# ik_dragonfly.net
KiCad netlist of a schematic drawn in EAGLE
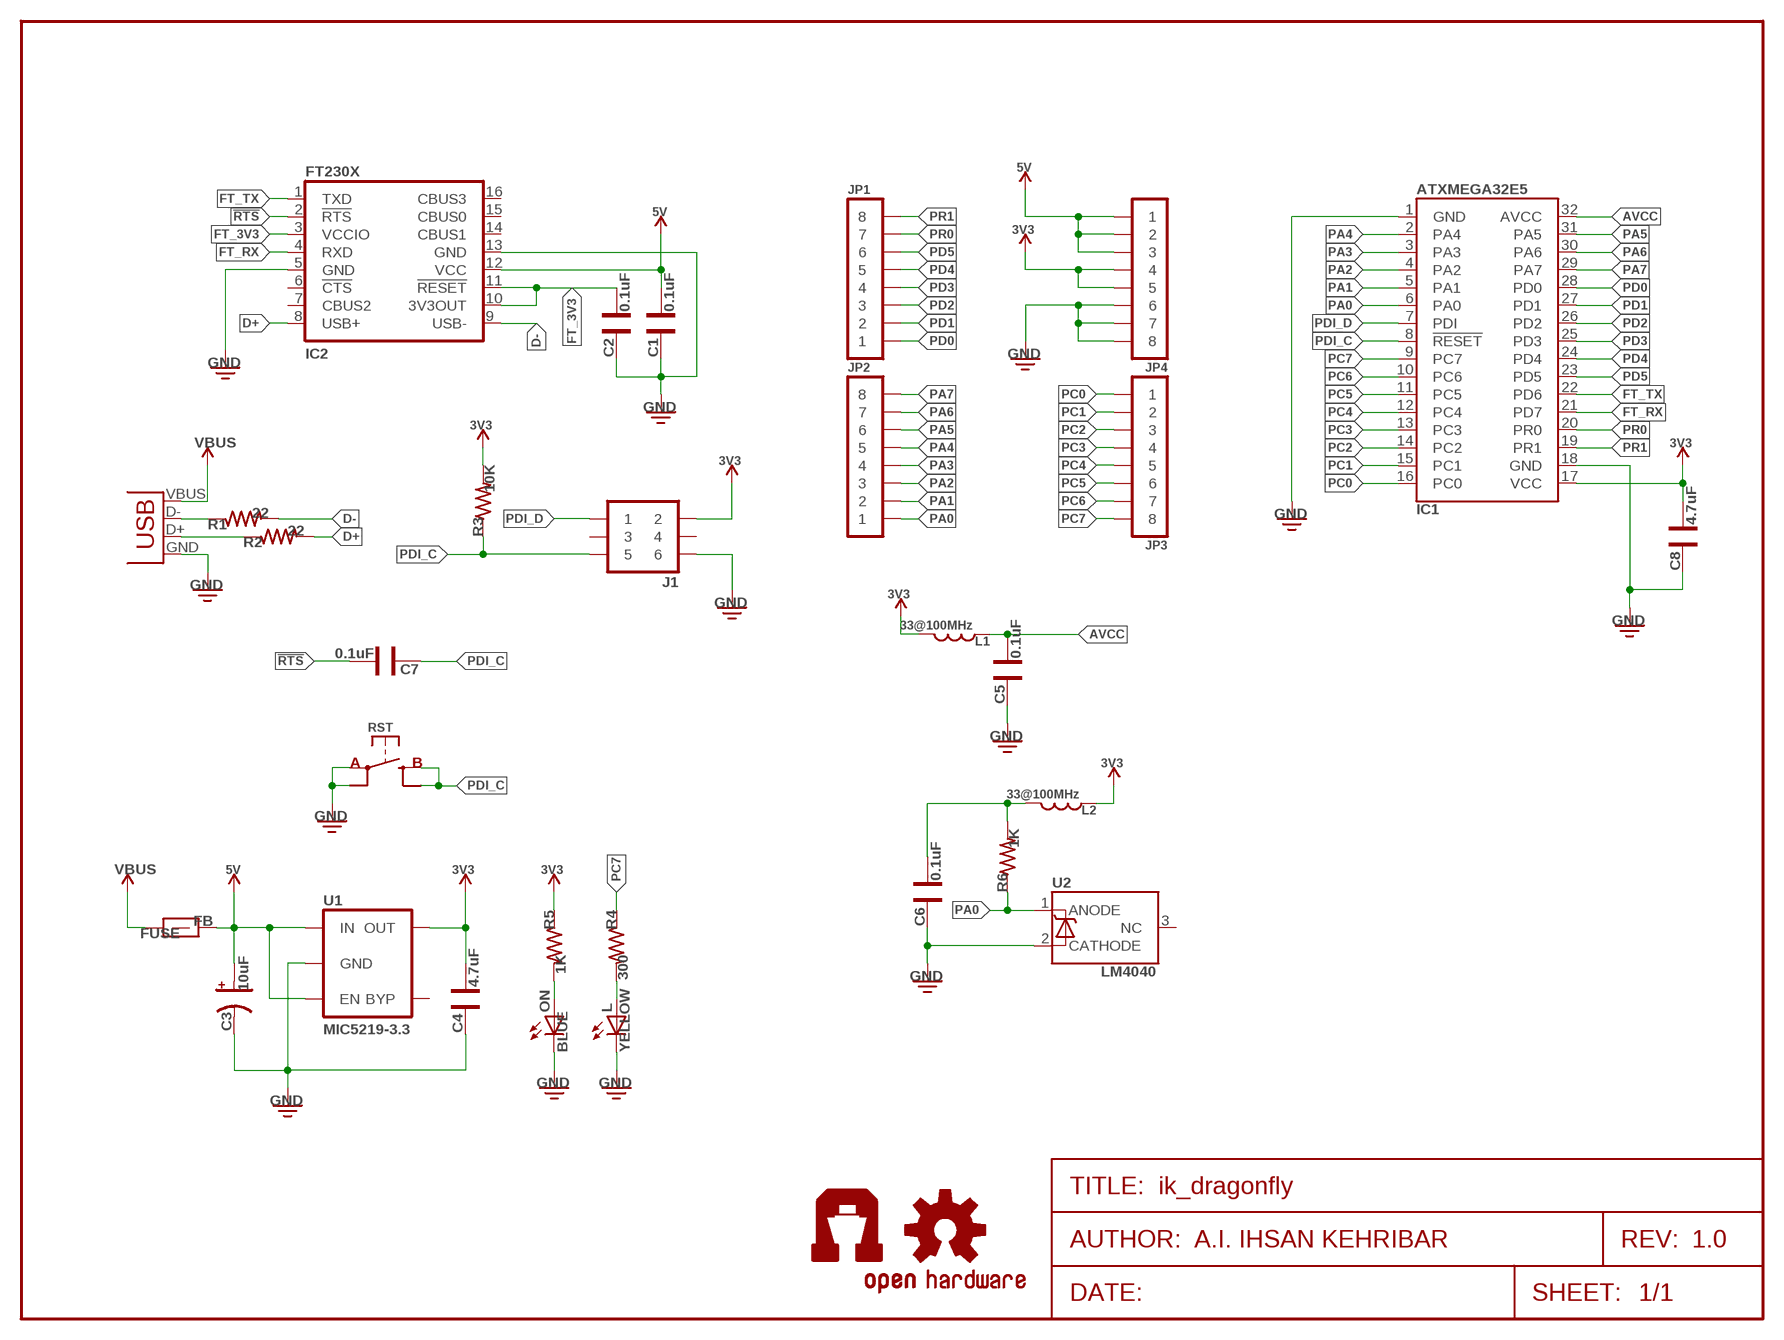
[diagram p0: schematic, sheet 1]

(export (version "E")
  (design (tool "Eeschema 10.0.6"))
  (components
    (comp (ref "C1")
      (value "0.1uF")
      (footprint "eagle-import:CAP-0603")
      (libsource (lib "eagle-import") (part "CAP0603"))
    )
    (comp (ref "C2")
      (value "0.1uF")
      (footprint "eagle-import:CAP-0603")
      (libsource (lib "eagle-import") (part "CAP0603"))
    )
    (comp (ref "C3")
      (value "10uF")
      (footprint "eagle-import:CAP-POL-EIA3216")
      (libsource (lib "eagle-import") (part "CAP-POLEIA3216"))
    )
    (comp (ref "C4")
      (value "4.7uF")
      (footprint "eagle-import:CAP-0603")
      (libsource (lib "eagle-import") (part "CAP0603"))
    )
    (comp (ref "C5")
      (value "0.1uF")
      (footprint "eagle-import:CAP-0603")
      (libsource (lib "eagle-import") (part "CAP0603"))
    )
    (comp (ref "C6")
      (value "0.1uF")
      (footprint "eagle-import:CAP-0603")
      (libsource (lib "eagle-import") (part "CAP0603"))
    )
    (comp (ref "C7")
      (value "0.1uF")
      (footprint "eagle-import:CAP-0603")
      (libsource (lib "eagle-import") (part "CAP0603"))
    )
    (comp (ref "C8")
      (value "4.7uF")
      (footprint "eagle-import:CAP-0603")
      (libsource (lib "eagle-import") (part "CAP0603"))
    )
    (comp (ref "FUSE")
      (value "FB")
      (footprint "eagle-import:FB-0603")
      (libsource (lib "eagle-import") (part "FB"))
    )
    (comp (ref "IC1")
      (value "ATXMEGA32E5")
      (footprint "eagle-import:TQFP32-08")
      (libsource (lib "eagle-import") (part "ATXMEGA32E5"))
    )
    (comp (ref "IC2")
      (value "FT230X")
      (footprint "eagle-import:SSOP-16-FTDI")
      (libsource (lib "eagle-import") (part "FT230X"))
    )
    (comp (ref "J1")
      (value "2X03")
      (footprint "eagle-import:2X03")
      (libsource (lib "eagle-import") (part "2X03"))
    )
    (comp (ref "JP1")
      (value "1X08NOFIRST")
      (footprint "eagle-import:1X08-NOFIRST")
      (libsource (lib "eagle-import") (part "1X08NOFIRST"))
    )
    (comp (ref "JP2")
      (value "1X08NOFIRST")
      (footprint "eagle-import:1X08-NOFIRST")
      (libsource (lib "eagle-import") (part "1X08NOFIRST"))
    )
    (comp (ref "JP3")
      (value "1X08NOFIRST")
      (footprint "eagle-import:1X08-NOFIRST")
      (libsource (lib "eagle-import") (part "1X08NOFIRST"))
    )
    (comp (ref "JP4")
      (value "1X08NOFIRST")
      (footprint "eagle-import:1X08-NOFIRST")
      (libsource (lib "eagle-import") (part "1X08NOFIRST"))
    )
    (comp (ref "L")
      (value "YELLOW")
      (footprint "eagle-import:LED-0603")
      (libsource (lib "eagle-import") (part "LED0603"))
    )
    (comp (ref "L1")
      (value "33@100MHz")
      (footprint "eagle-import:IND-0603")
      (libsource (lib "eagle-import") (part "IND0603"))
    )
    (comp (ref "L2")
      (value "33@100MHz")
      (footprint "eagle-import:IND-0603")
      (libsource (lib "eagle-import") (part "IND0603"))
    )
    (comp (ref "LOGO1")
      (value "OSHW-LOGOS")
      (footprint "eagle-import:OSHW-LOGO-S")
      (libsource (lib "eagle-import") (part "OSHW-LOGOS"))
    )
    (comp (ref "ON")
      (value "BLUE")
      (footprint "eagle-import:LED-0603")
      (libsource (lib "eagle-import") (part "LED0603"))
    )
    (comp (ref "R1")
      (value "22")
      (footprint "eagle-import:RES-0603")
      (libsource (lib "eagle-import") (part "RES0603"))
    )
    (comp (ref "R2")
      (value "22")
      (footprint "eagle-import:RES-0603")
      (libsource (lib "eagle-import") (part "RES0603"))
    )
    (comp (ref "R3")
      (value "10K")
      (footprint "eagle-import:RES-0603")
      (libsource (lib "eagle-import") (part "RES0603"))
    )
    (comp (ref "R4")
      (value "300")
      (footprint "eagle-import:RES-0603")
      (libsource (lib "eagle-import") (part "RES0603"))
    )
    (comp (ref "R5")
      (value "1K")
      (footprint "eagle-import:RES-0603")
      (libsource (lib "eagle-import") (part "RES0603"))
    )
    (comp (ref "R6")
      (value "1K")
      (footprint "eagle-import:RES-0603")
      (libsource (lib "eagle-import") (part "RES0603"))
    )
    (comp (ref "RST")
      (value "SW-SPSTSMD035X030")
      (footprint "eagle-import:SW-SPST-SMD035X030")
      (libsource (lib "eagle-import") (part "SW-SPSTSMD035X030"))
    )
    (comp (ref "U$3")
      (value "AI-LOGOXS")
      (footprint "eagle-import:AI-LOGO-XS")
      (libsource (lib "eagle-import") (part "AI-LOGOXS"))
    )
    (comp (ref "U1")
      (value "MIC5219-3.3")
      (footprint "eagle-import:SOT23-5")
      (libsource (lib "eagle-import") (part "MIC5219-3.3"))
    )
    (comp (ref "U2")
      (value "LM4040")
      (footprint "eagle-import:SOT23-3")
      (libsource (lib "eagle-import") (part "LM4040"))
    )
    (comp (ref "USB1")
      (value "USBMICROB-TH")
      (footprint "eagle-import:USB-MICROB-TH")
      (libsource (lib "eagle-import") (part "USBMICROB-TH"))
    )
  )
  (nets
    (net (code "1") (name "/~{RTS}") (class "Default")
      (node (ref "C7") (pin "1") (pinfunction "1_1") (pintype "passive"))
      (node (ref "IC2") (pin "2") (pinfunction "~{RTS}_2") (pintype "bidirectional"))
    )
    (net (code "2") (name "3V3") (class "Default")
      (node (ref "C4") (pin "1") (pinfunction "1_1") (pintype "passive"))
      (node (ref "C8") (pin "1") (pinfunction "1_1") (pintype "passive"))
      (node (ref "IC1") (pin "17") (pinfunction "VCC_17") (pintype "bidirectional"))
      (node (ref "J1") (pin "2") (pinfunction "2_2") (pintype "bidirectional"))
      (node (ref "JP4") (pin "4") (pinfunction "4_4") (pintype "bidirectional"))
      (node (ref "JP4") (pin "5") (pinfunction "5_5") (pintype "bidirectional"))
      (node (ref "L1") (pin "1") (pinfunction "1_1") (pintype "passive"))
      (node (ref "L2") (pin "2") (pinfunction "2_2") (pintype "passive"))
      (node (ref "R3") (pin "2") (pinfunction "2_2") (pintype "passive"))
      (node (ref "R5") (pin "1") (pinfunction "1_1") (pintype "passive"))
      (node (ref "U1") (pin "5") (pinfunction "OUT_5") (pintype "passive"))
    )
    (net (code "3") (name "5V") (class "Default")
      (node (ref "C1") (pin "1") (pinfunction "1_1") (pintype "passive"))
      (node (ref "C3") (pin "A") (pinfunction "A_A") (pintype "passive"))
      (node (ref "FUSE") (pin "2") (pinfunction "P$2_2") (pintype "bidirectional"))
      (node (ref "IC2") (pin "12") (pinfunction "VCC_12") (pintype "power_in"))
      (node (ref "JP4") (pin "1") (pinfunction "1_1") (pintype "bidirectional"))
      (node (ref "JP4") (pin "2") (pinfunction "2_2") (pintype "bidirectional"))
      (node (ref "JP4") (pin "3") (pinfunction "3_3") (pintype "bidirectional"))
      (node (ref "U1") (pin "1") (pinfunction "IN_1") (pintype "input"))
      (node (ref "U1") (pin "3") (pinfunction "EN_3") (pintype "input"))
    )
    (net (code "4") (name "AVCC") (class "Default")
      (node (ref "C5") (pin "1") (pinfunction "1_1") (pintype "passive"))
      (node (ref "IC1") (pin "32") (pinfunction "AVCC_32") (pintype "bidirectional"))
      (node (ref "L1") (pin "2") (pinfunction "2_2") (pintype "passive"))
    )
    (net (code "5") (name "D+") (class "Default")
      (node (ref "IC2") (pin "8") (pinfunction "USB+_8") (pintype "output"))
      (node (ref "R2") (pin "2") (pinfunction "2_2") (pintype "passive"))
    )
    (net (code "6") (name "D-") (class "Default")
      (node (ref "IC2") (pin "9") (pinfunction "USB-_9") (pintype "input"))
      (node (ref "R1") (pin "2") (pinfunction "2_2") (pintype "passive"))
    )
    (net (code "7") (name "FT_3V3") (class "Default")
      (node (ref "C2") (pin "1") (pinfunction "1_1") (pintype "passive"))
      (node (ref "IC2") (pin "10") (pinfunction "3V3OUT_10") (pintype "power_in"))
      (node (ref "IC2") (pin "11") (pinfunction "~{RESET}_11") (pintype "bidirectional"))
      (node (ref "IC2") (pin "3") (pinfunction "VCCIO_3") (pintype "power_in"))
    )
    (net (code "8") (name "FT_RX") (class "Default")
      (node (ref "IC1") (pin "21") (pinfunction "PD7_21") (pintype "bidirectional"))
      (node (ref "IC2") (pin "4") (pinfunction "RXD_4") (pintype "input"))
    )
    (net (code "9") (name "FT_TX") (class "Default")
      (node (ref "IC1") (pin "22") (pinfunction "PD6_22") (pintype "bidirectional"))
      (node (ref "IC2") (pin "1") (pinfunction "TXD_1") (pintype "output"))
    )
    (net (code "10") (name "GND") (class "Default")
      (node (ref "C1") (pin "2") (pinfunction "2_2") (pintype "passive"))
      (node (ref "C2") (pin "2") (pinfunction "2_2") (pintype "passive"))
      (node (ref "C3") (pin "C") (pinfunction "C_C") (pintype "passive"))
      (node (ref "C4") (pin "2") (pinfunction "2_2") (pintype "passive"))
      (node (ref "C5") (pin "2") (pinfunction "2_2") (pintype "passive"))
      (node (ref "C6") (pin "2") (pinfunction "2_2") (pintype "passive"))
      (node (ref "C8") (pin "2") (pinfunction "2_2") (pintype "passive"))
      (node (ref "IC1") (pin "1") (pinfunction "GND_1") (pintype "bidirectional"))
      (node (ref "IC1") (pin "18") (pinfunction "GND_18") (pintype "bidirectional"))
      (node (ref "IC2") (pin "13") (pinfunction "GND_13") (pintype "power_in"))
      (node (ref "IC2") (pin "5") (pinfunction "GND_5") (pintype "power_in"))
      (node (ref "J1") (pin "6") (pinfunction "6_6") (pintype "bidirectional"))
      (node (ref "JP4") (pin "6") (pinfunction "6_6") (pintype "bidirectional"))
      (node (ref "JP4") (pin "7") (pinfunction "7_7") (pintype "bidirectional"))
      (node (ref "JP4") (pin "8") (pinfunction "8_8") (pintype "bidirectional"))
      (node (ref "L") (pin "C") (pinfunction "C_C") (pintype "passive"))
      (node (ref "ON") (pin "C") (pinfunction "C_C") (pintype "passive"))
      (node (ref "RST") (pin "1") (pinfunction "A_1") (pintype "passive"))
      (node (ref "RST") (pin "2") (pinfunction "A_2") (pintype "passive"))
      (node (ref "U1") (pin "2") (pinfunction "GND_2") (pintype "input"))
      (node (ref "U2") (pin "2") (pinfunction "CATHODE_2") (pintype "bidirectional"))
      (node (ref "USB1") (pin "GND") (pinfunction "GND_GND") (pintype "bidirectional"))
    )
    (net (code "11") (name "Net-(C6-Pad1)") (class "Default")
      (node (ref "C6") (pin "1") (pinfunction "1_1") (pintype "passive"))
      (node (ref "L2") (pin "1") (pinfunction "1_1") (pintype "passive"))
      (node (ref "R6") (pin "2") (pinfunction "2_2") (pintype "passive"))
    )
    (net (code "12") (name "Net-(L-PadA)") (class "Default")
      (node (ref "L") (pin "A") (pinfunction "A_A") (pintype "passive"))
      (node (ref "R4") (pin "2") (pinfunction "2_2") (pintype "passive"))
    )
    (net (code "13") (name "Net-(ON-PadA)") (class "Default")
      (node (ref "ON") (pin "A") (pinfunction "A_A") (pintype "passive"))
      (node (ref "R5") (pin "2") (pinfunction "2_2") (pintype "passive"))
    )
    (net (code "14") (name "Net-(R1-Pad1)") (class "Default")
      (node (ref "R1") (pin "1") (pinfunction "1_1") (pintype "passive"))
      (node (ref "USB1") (pin "D-") (pinfunction "D-_D-") (pintype "bidirectional"))
    )
    (net (code "15") (name "Net-(R2-Pad1)") (class "Default")
      (node (ref "R2") (pin "1") (pinfunction "1_1") (pintype "passive"))
      (node (ref "USB1") (pin "D+") (pinfunction "D+_D+") (pintype "bidirectional"))
    )
    (net (code "16") (name "PA0") (class "Default")
      (node (ref "IC1") (pin "6") (pinfunction "PA0_6") (pintype "bidirectional"))
      (node (ref "JP2") (pin "1") (pinfunction "1_1") (pintype "bidirectional"))
      (node (ref "R6") (pin "1") (pinfunction "1_1") (pintype "passive"))
      (node (ref "U2") (pin "1") (pinfunction "ANODE_1") (pintype "bidirectional"))
    )
    (net (code "17") (name "PA1") (class "Default")
      (node (ref "IC1") (pin "5") (pinfunction "PA1_5") (pintype "bidirectional"))
      (node (ref "JP2") (pin "2") (pinfunction "2_2") (pintype "bidirectional"))
    )
    (net (code "18") (name "PA2") (class "Default")
      (node (ref "IC1") (pin "4") (pinfunction "PA2_4") (pintype "bidirectional"))
      (node (ref "JP2") (pin "3") (pinfunction "3_3") (pintype "bidirectional"))
    )
    (net (code "19") (name "PA3") (class "Default")
      (node (ref "IC1") (pin "3") (pinfunction "PA3_3") (pintype "bidirectional"))
      (node (ref "JP2") (pin "4") (pinfunction "4_4") (pintype "bidirectional"))
    )
    (net (code "20") (name "PA4") (class "Default")
      (node (ref "IC1") (pin "2") (pinfunction "PA4_2") (pintype "bidirectional"))
      (node (ref "JP2") (pin "5") (pinfunction "5_5") (pintype "bidirectional"))
    )
    (net (code "21") (name "PA5") (class "Default")
      (node (ref "IC1") (pin "31") (pinfunction "PA5_31") (pintype "bidirectional"))
      (node (ref "JP2") (pin "6") (pinfunction "6_6") (pintype "bidirectional"))
    )
    (net (code "22") (name "PA6") (class "Default")
      (node (ref "IC1") (pin "30") (pinfunction "PA6_30") (pintype "bidirectional"))
      (node (ref "JP2") (pin "7") (pinfunction "7_7") (pintype "bidirectional"))
    )
    (net (code "23") (name "PA7") (class "Default")
      (node (ref "IC1") (pin "29") (pinfunction "PA7_29") (pintype "bidirectional"))
      (node (ref "JP2") (pin "8") (pinfunction "8_8") (pintype "bidirectional"))
    )
    (net (code "24") (name "PC0") (class "Default")
      (node (ref "IC1") (pin "16") (pinfunction "PC0_16") (pintype "bidirectional"))
      (node (ref "JP3") (pin "1") (pinfunction "1_1") (pintype "bidirectional"))
    )
    (net (code "25") (name "PC1") (class "Default")
      (node (ref "IC1") (pin "15") (pinfunction "PC1_15") (pintype "bidirectional"))
      (node (ref "JP3") (pin "2") (pinfunction "2_2") (pintype "bidirectional"))
    )
    (net (code "26") (name "PC2") (class "Default")
      (node (ref "IC1") (pin "14") (pinfunction "PC2_14") (pintype "bidirectional"))
      (node (ref "JP3") (pin "3") (pinfunction "3_3") (pintype "bidirectional"))
    )
    (net (code "27") (name "PC3") (class "Default")
      (node (ref "IC1") (pin "13") (pinfunction "PC3_13") (pintype "bidirectional"))
      (node (ref "JP3") (pin "4") (pinfunction "4_4") (pintype "bidirectional"))
    )
    (net (code "28") (name "PC4") (class "Default")
      (node (ref "IC1") (pin "12") (pinfunction "PC4_12") (pintype "bidirectional"))
      (node (ref "JP3") (pin "5") (pinfunction "5_5") (pintype "bidirectional"))
    )
    (net (code "29") (name "PC5") (class "Default")
      (node (ref "IC1") (pin "11") (pinfunction "PC5_11") (pintype "bidirectional"))
      (node (ref "JP3") (pin "6") (pinfunction "6_6") (pintype "bidirectional"))
    )
    (net (code "30") (name "PC6") (class "Default")
      (node (ref "IC1") (pin "10") (pinfunction "PC6_10") (pintype "bidirectional"))
      (node (ref "JP3") (pin "7") (pinfunction "7_7") (pintype "bidirectional"))
    )
    (net (code "31") (name "PC7") (class "Default")
      (node (ref "IC1") (pin "9") (pinfunction "PC7_9") (pintype "bidirectional"))
      (node (ref "JP3") (pin "8") (pinfunction "8_8") (pintype "bidirectional"))
      (node (ref "R4") (pin "1") (pinfunction "1_1") (pintype "passive"))
    )
    (net (code "32") (name "PD0") (class "Default")
      (node (ref "IC1") (pin "28") (pinfunction "PD0_28") (pintype "bidirectional"))
      (node (ref "JP1") (pin "1") (pinfunction "1_1") (pintype "bidirectional"))
    )
    (net (code "33") (name "PD1") (class "Default")
      (node (ref "IC1") (pin "27") (pinfunction "PD1_27") (pintype "bidirectional"))
      (node (ref "JP1") (pin "2") (pinfunction "2_2") (pintype "bidirectional"))
    )
    (net (code "34") (name "PD2") (class "Default")
      (node (ref "IC1") (pin "26") (pinfunction "PD2_26") (pintype "bidirectional"))
      (node (ref "JP1") (pin "3") (pinfunction "3_3") (pintype "bidirectional"))
    )
    (net (code "35") (name "PD3") (class "Default")
      (node (ref "IC1") (pin "25") (pinfunction "PD3_25") (pintype "bidirectional"))
      (node (ref "JP1") (pin "4") (pinfunction "4_4") (pintype "bidirectional"))
    )
    (net (code "36") (name "PD4") (class "Default")
      (node (ref "IC1") (pin "24") (pinfunction "PD4_24") (pintype "bidirectional"))
      (node (ref "JP1") (pin "5") (pinfunction "5_5") (pintype "bidirectional"))
    )
    (net (code "37") (name "PD5") (class "Default")
      (node (ref "IC1") (pin "23") (pinfunction "PD5_23") (pintype "bidirectional"))
      (node (ref "JP1") (pin "6") (pinfunction "6_6") (pintype "bidirectional"))
    )
    (net (code "38") (name "PDI_C") (class "Default")
      (node (ref "C7") (pin "2") (pinfunction "2_2") (pintype "passive"))
      (node (ref "IC1") (pin "8") (pinfunction "~{RESET}_8") (pintype "bidirectional"))
      (node (ref "J1") (pin "5") (pinfunction "5_5") (pintype "bidirectional"))
      (node (ref "R3") (pin "1") (pinfunction "1_1") (pintype "passive"))
      (node (ref "RST") (pin "3") (pinfunction "B_3") (pintype "passive"))
      (node (ref "RST") (pin "4") (pinfunction "B_4") (pintype "passive"))
    )
    (net (code "39") (name "PDI_D") (class "Default")
      (node (ref "IC1") (pin "7") (pinfunction "PDI_7") (pintype "bidirectional"))
      (node (ref "J1") (pin "1") (pinfunction "1_1") (pintype "bidirectional"))
    )
    (net (code "40") (name "PR0") (class "Default")
      (node (ref "IC1") (pin "20") (pinfunction "PR0_20") (pintype "bidirectional"))
      (node (ref "JP1") (pin "7") (pinfunction "7_7") (pintype "bidirectional"))
    )
    (net (code "41") (name "PR1") (class "Default")
      (node (ref "IC1") (pin "19") (pinfunction "PR1_19") (pintype "bidirectional"))
      (node (ref "JP1") (pin "8") (pinfunction "8_8") (pintype "bidirectional"))
    )
    (net (code "42") (name "VBUS") (class "Default")
      (node (ref "FUSE") (pin "1") (pinfunction "P$1_1") (pintype "passive"))
      (node (ref "USB1") (pin "VBUS") (pinfunction "VBUS_VBUS") (pintype "bidirectional"))
    )
    (net (code "43") (name "unconnected-(IC2-CBUS0-Pad15)") (class "Default")
      (node (ref "IC2") (pin "15") (pinfunction "CBUS0_15") (pintype "bidirectional"))
    )
    (net (code "44") (name "unconnected-(IC2-CBUS1-Pad14)") (class "Default")
      (node (ref "IC2") (pin "14") (pinfunction "CBUS1_14") (pintype "bidirectional"))
    )
    (net (code "45") (name "unconnected-(IC2-CBUS2-Pad7)") (class "Default")
      (node (ref "IC2") (pin "7") (pinfunction "CBUS2_7") (pintype "bidirectional"))
    )
    (net (code "46") (name "unconnected-(IC2-CBUS3-Pad16)") (class "Default")
      (node (ref "IC2") (pin "16") (pinfunction "CBUS3_16") (pintype "bidirectional"))
    )
    (net (code "47") (name "unconnected-(IC2-~{CTS}-Pad6)") (class "Default")
      (node (ref "IC2") (pin "6") (pinfunction "~{CTS}_6") (pintype "bidirectional"))
    )
    (net (code "48") (name "unconnected-(J1-Pad3)") (class "Default")
      (node (ref "J1") (pin "3") (pinfunction "3_3") (pintype "bidirectional"))
    )
    (net (code "49") (name "unconnected-(J1-Pad4)") (class "Default")
      (node (ref "J1") (pin "4") (pinfunction "4_4") (pintype "bidirectional"))
    )
    (net (code "50") (name "unconnected-(U1-BYP-Pad4)") (class "Default")
      (node (ref "U1") (pin "4") (pinfunction "BYP_4") (pintype "input"))
    )
    (net (code "51") (name "unconnected-(U2-NC-Pad3)") (class "Default")
      (node (ref "U2") (pin "3") (pinfunction "NC_3") (pintype "bidirectional"))
    )
  )
)
